# 467444_130_3_5-R0.net
KiCad netlist of a schematic drawn in Altium Designer
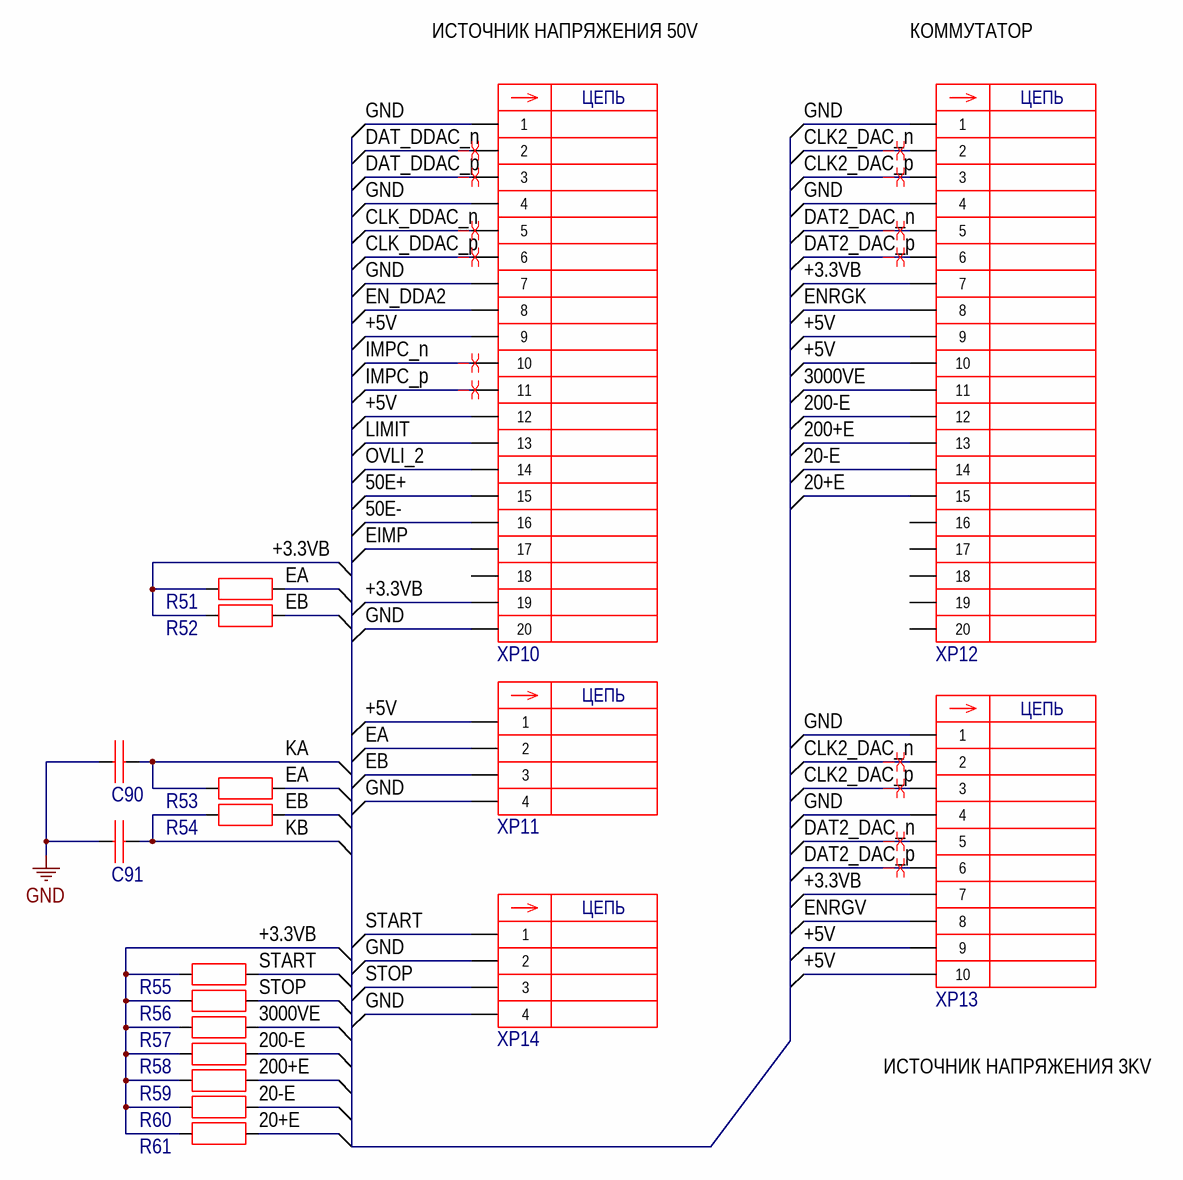
[diagram p0: УШЯИ.467444.130Э3_5-R0.SchDoc]

(export (version "E")
  (design (tool "Eeschema 10.0.6"))
  (components
    (comp (ref "C90")
      (value "0,1 µF")
      (footprint "C_0805 [2012 Metric]")
      (description "Неполярный конденсатор")
      (fields (field (name "MANUFACTURER") "Murata") (field (name "VOLTAGE") "50V"))
      (libsource (lib "lib") (part "C_const"))
    )
    (comp (ref "C91")
      (value "0,1 µF")
      (footprint "C_0805 [2012 Metric]")
      (description "Неполярный конденсатор")
      (fields (field (name "MANUFACTURER") "Murata") (field (name "VOLTAGE") "50V"))
      (libsource (lib "lib") (part "C_const"))
    )
    (comp (ref "R51")
      (value "10k")
      (footprint "R_0805 [2012 Metric]")
      (fields (field (name "TOLERANCE") "±1%"))
      (libsource (lib "lib") (part "R_Const"))
    )
    (comp (ref "R52")
      (value "10k")
      (footprint "R_0805 [2012 Metric]")
      (fields (field (name "TOLERANCE") "±1%"))
      (libsource (lib "lib") (part "R_Const"))
    )
    (comp (ref "R53")
      (value "10k")
      (footprint "R_0805 [2012 Metric]")
      (fields (field (name "TOLERANCE") "±1%"))
      (libsource (lib "lib") (part "R_Const"))
    )
    (comp (ref "R54")
      (value "10k")
      (footprint "R_0805 [2012 Metric]")
      (fields (field (name "TOLERANCE") "±1%"))
      (libsource (lib "lib") (part "R_Const"))
    )
    (comp (ref "R55")
      (value "10k")
      (footprint "R_0805 [2012 Metric]")
      (fields (field (name "TOLERANCE") "±1%"))
      (libsource (lib "lib") (part "R_Const"))
    )
    (comp (ref "R56")
      (value "10k")
      (footprint "R_0805 [2012 Metric]")
      (fields (field (name "TOLERANCE") "±1%"))
      (libsource (lib "lib") (part "R_Const"))
    )
    (comp (ref "R57")
      (value "10k")
      (footprint "R_0805 [2012 Metric]")
      (fields (field (name "TOLERANCE") "±1%"))
      (libsource (lib "lib") (part "R_Const"))
    )
    (comp (ref "R58")
      (value "10k")
      (footprint "R_0805 [2012 Metric]")
      (fields (field (name "TOLERANCE") "±1%"))
      (libsource (lib "lib") (part "R_Const"))
    )
    (comp (ref "R59")
      (value "10k")
      (footprint "R_0805 [2012 Metric]")
      (fields (field (name "TOLERANCE") "±1%"))
      (libsource (lib "lib") (part "R_Const"))
    )
    (comp (ref "R60")
      (value "10k")
      (footprint "R_0805 [2012 Metric]")
      (fields (field (name "TOLERANCE") "±1%"))
      (libsource (lib "lib") (part "R_Const"))
    )
    (comp (ref "R61")
      (value "10k")
      (footprint "R_0805 [2012 Metric]")
      (fields (field (name "TOLERANCE") "±1%"))
      (libsource (lib "lib") (part "R_Const"))
    )
    (comp (ref "XP10")
      (value "BH2-20R")
      (footprint "BH2-20R")
      (description "Male, 20 pins, 2 rows, Right Angle, DS1014-20RF1B-B, 2 mm")
      (fields (field (name "MANUFACTURER") "Connfly electronic"))
      (libsource (lib "lib") (part "M_20"))
    )
    (comp (ref "XP11")
      (value "AMPMODU II 280371-2")
      (footprint "AMP II-280371-2")
      (description "Male, 4 pin, 1 row, Vertical, Board-to-Board, 2.54 mm")
      (fields (field (name "MANUFACTURER") "TE Connectivity"))
      (libsource (lib "lib") (part "M_4"))
    )
    (comp (ref "XP12")
      (value "BH2-20R")
      (footprint "BH2-20R")
      (description "Male, 20 pins, 2 rows, Right Angle, DS1014-20RF1B-B, 2 mm")
      (fields (field (name "MANUFACTURER") "Connfly electronic"))
      (libsource (lib "lib") (part "M_20"))
    )
    (comp (ref "XP13")
      (value "BH2-10R")
      (footprint "BH2-10R")
      (description "Male, 10 pins, 2 rows, Vertical, DS1014-10RF1B-B, 2 mm")
      (fields (field (name "MANUFACTURER") "Connfly electronic"))
      (libsource (lib "lib") (part "M_10"))
    )
    (comp (ref "XP14")
      (value "AMPMODU II 280371-2")
      (footprint "AMP II-280371-2")
      (description "Male, 4 pin, 1 row, Vertical, Board-to-Board, 2.54 mm")
      (fields (field (name "MANUFACTURER") "TE Connectivity"))
      (libsource (lib "lib") (part "M_4"))
    )
  )
  (nets
    (net (code "1") (name "/+3.3VB") (class "Default")
      (node (ref "R51") (pin "1") (pinfunction "1_1") (pintype "passive"))
      (node (ref "R52") (pin "1") (pinfunction "1_1") (pintype "passive"))
      (node (ref "R55") (pin "1") (pinfunction "1_1") (pintype "passive"))
      (node (ref "R56") (pin "1") (pinfunction "1_1") (pintype "passive"))
      (node (ref "R57") (pin "1") (pinfunction "1_1") (pintype "passive"))
      (node (ref "R58") (pin "1") (pinfunction "1_1") (pintype "passive"))
      (node (ref "R59") (pin "1") (pinfunction "1_1") (pintype "passive"))
      (node (ref "R60") (pin "1") (pinfunction "1_1") (pintype "passive"))
      (node (ref "R61") (pin "1") (pinfunction "1_1") (pintype "passive"))
      (node (ref "XP10") (pin "19") (pinfunction "19_19") (pintype "passive"))
      (node (ref "XP12") (pin "7") (pinfunction "7_7") (pintype "passive"))
      (node (ref "XP13") (pin "7") (pinfunction "7_7") (pintype "passive"))
    )
    (net (code "2") (name "/+5V") (class "Default")
      (node (ref "XP10") (pin "12") (pinfunction "12_12") (pintype "passive"))
      (node (ref "XP10") (pin "9") (pinfunction "9_9") (pintype "passive"))
      (node (ref "XP11") (pin "1") (pinfunction "1_1") (pintype "passive"))
      (node (ref "XP12") (pin "10") (pinfunction "10_10") (pintype "passive"))
      (node (ref "XP12") (pin "9") (pinfunction "9_9") (pintype "passive"))
      (node (ref "XP13") (pin "10") (pinfunction "10_10") (pintype "passive"))
      (node (ref "XP13") (pin "9") (pinfunction "9_9") (pintype "passive"))
    )
    (net (code "3") (name "/20+E") (class "Default")
      (node (ref "R61") (pin "2") (pinfunction "2_2") (pintype "passive"))
      (node (ref "XP12") (pin "15") (pinfunction "15_15") (pintype "passive"))
    )
    (net (code "4") (name "/20-E") (class "Default")
      (node (ref "R60") (pin "2") (pinfunction "2_2") (pintype "passive"))
      (node (ref "XP12") (pin "14") (pinfunction "14_14") (pintype "passive"))
    )
    (net (code "5") (name "/50E+") (class "Default")
      (node (ref "XP10") (pin "15") (pinfunction "15_15") (pintype "passive"))
    )
    (net (code "6") (name "/50E-") (class "Default")
      (node (ref "XP10") (pin "16") (pinfunction "16_16") (pintype "passive"))
    )
    (net (code "7") (name "/200+E") (class "Default")
      (node (ref "R59") (pin "2") (pinfunction "2_2") (pintype "passive"))
      (node (ref "XP12") (pin "13") (pinfunction "13_13") (pintype "passive"))
    )
    (net (code "8") (name "/200-E") (class "Default")
      (node (ref "R58") (pin "2") (pinfunction "2_2") (pintype "passive"))
      (node (ref "XP12") (pin "12") (pinfunction "12_12") (pintype "passive"))
    )
    (net (code "9") (name "/3000VE") (class "Default")
      (node (ref "R57") (pin "2") (pinfunction "2_2") (pintype "passive"))
      (node (ref "XP12") (pin "11") (pinfunction "11_11") (pintype "passive"))
    )
    (net (code "10") (name "/CLK2_DAC_n") (class "Default")
      (node (ref "XP12") (pin "2") (pinfunction "2_2") (pintype "passive"))
      (node (ref "XP13") (pin "2") (pinfunction "2_2") (pintype "passive"))
    )
    (net (code "11") (name "/CLK2_DAC_p") (class "Default")
      (node (ref "XP12") (pin "3") (pinfunction "3_3") (pintype "passive"))
      (node (ref "XP13") (pin "3") (pinfunction "3_3") (pintype "passive"))
    )
    (net (code "12") (name "/CLK_DDAC_n") (class "Default")
      (node (ref "XP10") (pin "5") (pinfunction "5_5") (pintype "passive"))
    )
    (net (code "13") (name "/CLK_DDAC_p") (class "Default")
      (node (ref "XP10") (pin "6") (pinfunction "6_6") (pintype "passive"))
    )
    (net (code "14") (name "/DAT2_DAC_n") (class "Default")
      (node (ref "XP12") (pin "5") (pinfunction "5_5") (pintype "passive"))
      (node (ref "XP13") (pin "5") (pinfunction "5_5") (pintype "passive"))
    )
    (net (code "15") (name "/DAT2_DAC_p") (class "Default")
      (node (ref "XP12") (pin "6") (pinfunction "6_6") (pintype "passive"))
      (node (ref "XP13") (pin "6") (pinfunction "6_6") (pintype "passive"))
    )
    (net (code "16") (name "/DAT_DDAC_n") (class "Default")
      (node (ref "XP10") (pin "2") (pinfunction "2_2") (pintype "passive"))
    )
    (net (code "17") (name "/DAT_DDAC_p") (class "Default")
      (node (ref "XP10") (pin "3") (pinfunction "3_3") (pintype "passive"))
    )
    (net (code "18") (name "/EA") (class "Default")
      (node (ref "R51") (pin "2") (pinfunction "2_2") (pintype "passive"))
      (node (ref "R53") (pin "2") (pinfunction "2_2") (pintype "passive"))
      (node (ref "XP11") (pin "2") (pinfunction "2_2") (pintype "passive"))
    )
    (net (code "19") (name "/EB") (class "Default")
      (node (ref "R52") (pin "2") (pinfunction "2_2") (pintype "passive"))
      (node (ref "R54") (pin "2") (pinfunction "2_2") (pintype "passive"))
      (node (ref "XP11") (pin "3") (pinfunction "3_3") (pintype "passive"))
    )
    (net (code "20") (name "/EIMP") (class "Default")
      (node (ref "XP10") (pin "17") (pinfunction "17_17") (pintype "passive"))
    )
    (net (code "21") (name "/ENRGK") (class "Default")
      (node (ref "XP12") (pin "8") (pinfunction "8_8") (pintype "passive"))
    )
    (net (code "22") (name "/ENRGV") (class "Default")
      (node (ref "XP13") (pin "8") (pinfunction "8_8") (pintype "passive"))
    )
    (net (code "23") (name "/EN_DDA2") (class "Default")
      (node (ref "XP10") (pin "8") (pinfunction "8_8") (pintype "passive"))
    )
    (net (code "24") (name "/IMPC_n") (class "Default")
      (node (ref "XP10") (pin "10") (pinfunction "10_10") (pintype "passive"))
    )
    (net (code "25") (name "/IMPC_p") (class "Default")
      (node (ref "XP10") (pin "11") (pinfunction "11_11") (pintype "passive"))
    )
    (net (code "26") (name "/KA") (class "Default")
      (node (ref "C90") (pin "1") (pinfunction "1_1") (pintype "passive"))
      (node (ref "R53") (pin "1") (pinfunction "1_1") (pintype "passive"))
    )
    (net (code "27") (name "/KB") (class "Default")
      (node (ref "C91") (pin "1") (pinfunction "1_1") (pintype "passive"))
      (node (ref "R54") (pin "1") (pinfunction "1_1") (pintype "passive"))
    )
    (net (code "28") (name "/LIMIT") (class "Default")
      (node (ref "XP10") (pin "13") (pinfunction "13_13") (pintype "passive"))
    )
    (net (code "29") (name "/OVLI_2") (class "Default")
      (node (ref "XP10") (pin "14") (pinfunction "14_14") (pintype "passive"))
    )
    (net (code "30") (name "/START") (class "Default")
      (node (ref "R55") (pin "2") (pinfunction "2_2") (pintype "passive"))
      (node (ref "XP14") (pin "1") (pinfunction "1_1") (pintype "passive"))
    )
    (net (code "31") (name "/STOP") (class "Default")
      (node (ref "R56") (pin "2") (pinfunction "2_2") (pintype "passive"))
      (node (ref "XP14") (pin "3") (pinfunction "3_3") (pintype "passive"))
    )
    (net (code "32") (name "GND") (class "Default")
      (node (ref "C90") (pin "2") (pinfunction "2_2") (pintype "passive"))
      (node (ref "C91") (pin "2") (pinfunction "2_2") (pintype "passive"))
      (node (ref "XP10") (pin "1") (pinfunction "1_1") (pintype "passive"))
      (node (ref "XP10") (pin "20") (pinfunction "20_20") (pintype "passive"))
      (node (ref "XP10") (pin "4") (pinfunction "4_4") (pintype "passive"))
      (node (ref "XP10") (pin "7") (pinfunction "7_7") (pintype "passive"))
      (node (ref "XP11") (pin "4") (pinfunction "4_4") (pintype "passive"))
      (node (ref "XP12") (pin "1") (pinfunction "1_1") (pintype "passive"))
      (node (ref "XP12") (pin "4") (pinfunction "4_4") (pintype "passive"))
      (node (ref "XP13") (pin "1") (pinfunction "1_1") (pintype "passive"))
      (node (ref "XP13") (pin "4") (pinfunction "4_4") (pintype "passive"))
      (node (ref "XP14") (pin "2") (pinfunction "2_2") (pintype "passive"))
      (node (ref "XP14") (pin "4") (pinfunction "4_4") (pintype "passive"))
    )
    (net (code "33") (name "unconnected-(XP10-Pad18)") (class "Default")
      (node (ref "XP10") (pin "18") (pinfunction "18_18") (pintype "passive"))
    )
    (net (code "34") (name "unconnected-(XP12-Pad16)") (class "Default")
      (node (ref "XP12") (pin "16") (pinfunction "16_16") (pintype "passive"))
    )
    (net (code "35") (name "unconnected-(XP12-Pad17)") (class "Default")
      (node (ref "XP12") (pin "17") (pinfunction "17_17") (pintype "passive"))
    )
    (net (code "36") (name "unconnected-(XP12-Pad18)") (class "Default")
      (node (ref "XP12") (pin "18") (pinfunction "18_18") (pintype "passive"))
    )
    (net (code "37") (name "unconnected-(XP12-Pad19)") (class "Default")
      (node (ref "XP12") (pin "19") (pinfunction "19_19") (pintype "passive"))
    )
    (net (code "38") (name "unconnected-(XP12-Pad20)") (class "Default")
      (node (ref "XP12") (pin "20") (pinfunction "20_20") (pintype "passive"))
    )
  )
)
